# schema.net
KiCad netlist of a schematic drawn in EAGLE
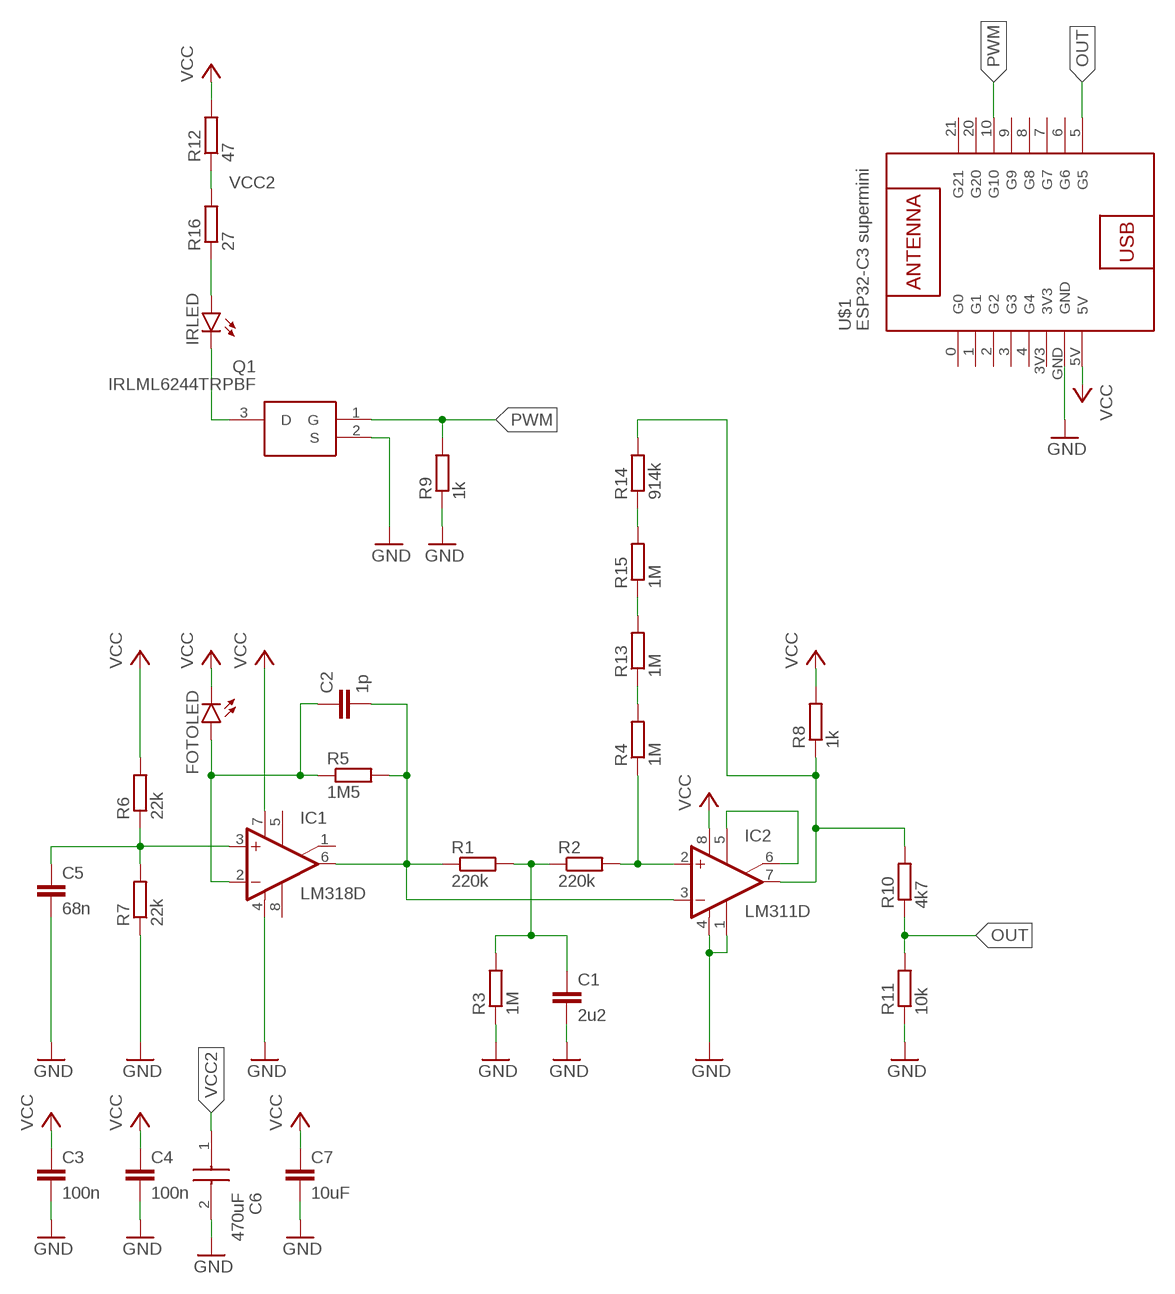
[diagram p0: schematic, sheet 1]

(export (version "E")
  (design (tool "Eeschema 10.0.6"))
  (components
    (comp (ref "C1")
      (value "2u2")
      (footprint "eagle-import:C0603")
      (libsource (lib "eagle-import") (part "C-EUC0603"))
    )
    (comp (ref "C2")
      (value "1p")
      (footprint "eagle-import:C0603K")
      (libsource (lib "eagle-import") (part "C-EUC0603K"))
    )
    (comp (ref "C3")
      (value "100n")
      (footprint "eagle-import:C0603")
      (libsource (lib "eagle-import") (part "C-EUC0603"))
    )
    (comp (ref "C4")
      (value "100n")
      (footprint "eagle-import:C0603")
      (libsource (lib "eagle-import") (part "C-EUC0603"))
    )
    (comp (ref "C5")
      (value "68n")
      (footprint "eagle-import:C0603")
      (libsource (lib "eagle-import") (part "C-EUC0603"))
    )
    (comp (ref "C6")
      (value "470uF")
      (footprint "eagle-import:CAPAE830X1100N")
      (fields (field (name "MANUFACTURER_PART_NUMBER") "AEA0810101M035R"))
      (libsource (lib "eagle-import") (part "AEA0810101M035R"))
    )
    (comp (ref "C7")
      (value "10uF")
      (footprint "eagle-import:C0603")
      (libsource (lib "eagle-import") (part "C-EUC0603"))
    )
    (comp (ref "FOTOLED")
      (value "LED5MM")
      (footprint "eagle-import:LED5MM")
      (libsource (lib "eagle-import") (part "LED5MM"))
    )
    (comp (ref "IC1")
      (value "LM318D")
      (footprint "eagle-import:SO08")
      (libsource (lib "eagle-import") (part "LM318D"))
    )
    (comp (ref "IC2")
      (value "LM311D")
      (footprint "eagle-import:SO08")
      (libsource (lib "eagle-import") (part "LM311D"))
    )
    (comp (ref "IRLED")
      (value "LED5MM")
      (footprint "eagle-import:LED5MM")
      (libsource (lib "eagle-import") (part "LED5MM"))
    )
    (comp (ref "Q1")
      (value "IRLML6244TRPBF")
      (footprint "eagle-import:SOT95P237X112-3N")
      (libsource (lib "eagle-import") (part "IRLML6244TRPBF"))
    )
    (comp (ref "R1")
      (value "220k")
      (footprint "eagle-import:R0603")
      (libsource (lib "eagle-import") (part "R-EU_R0603"))
    )
    (comp (ref "R2")
      (value "220k")
      (footprint "eagle-import:R0603")
      (libsource (lib "eagle-import") (part "R-EU_R0603"))
    )
    (comp (ref "R3")
      (value "1M")
      (footprint "eagle-import:R0603")
      (libsource (lib "eagle-import") (part "R-EU_R0603"))
    )
    (comp (ref "R4")
      (value "1M")
      (footprint "eagle-import:R0603")
      (libsource (lib "eagle-import") (part "R-EU_R0603"))
    )
    (comp (ref "R5")
      (value "1M5")
      (footprint "eagle-import:R0603")
      (libsource (lib "eagle-import") (part "R-EU_R0603"))
    )
    (comp (ref "R6")
      (value "22k")
      (footprint "eagle-import:R0603")
      (libsource (lib "eagle-import") (part "R-EU_R0603"))
    )
    (comp (ref "R7")
      (value "22k")
      (footprint "eagle-import:R0603")
      (libsource (lib "eagle-import") (part "R-EU_R0603"))
    )
    (comp (ref "R8")
      (value "1k")
      (footprint "eagle-import:R0603")
      (libsource (lib "eagle-import") (part "R-EU_R0603"))
    )
    (comp (ref "R9")
      (value "1k")
      (footprint "eagle-import:R0603")
      (libsource (lib "eagle-import") (part "R-EU_R0603"))
    )
    (comp (ref "R10")
      (value "4k7")
      (footprint "eagle-import:R0603")
      (libsource (lib "eagle-import") (part "R-EU_R0603"))
    )
    (comp (ref "R11")
      (value "10k")
      (footprint "eagle-import:R0603")
      (libsource (lib "eagle-import") (part "R-EU_R0603"))
    )
    (comp (ref "R12")
      (value "47")
      (footprint "eagle-import:R0805")
      (libsource (lib "eagle-import") (part "R-EU_R0805"))
    )
    (comp (ref "R13")
      (value "1M")
      (footprint "eagle-import:R0603")
      (libsource (lib "eagle-import") (part "R-EU_R0603"))
    )
    (comp (ref "R14")
      (value "914k")
      (footprint "eagle-import:R0603")
      (libsource (lib "eagle-import") (part "R-EU_R0603"))
    )
    (comp (ref "R15")
      (value "1M")
      (footprint "eagle-import:R0603")
      (libsource (lib "eagle-import") (part "R-EU_R0603"))
    )
    (comp (ref "R16")
      (value "27")
      (footprint "eagle-import:R0805")
      (libsource (lib "eagle-import") (part "R-EU_R0805"))
    )
    (comp (ref "U$1")
      (value "ESP32-C3 supermini")
      (footprint "eagle-import:ESP32-C3_SUPERMINI")
      (libsource (lib "eagle-import") (part "ESP32-C3_SUPERMINI"))
    )
  )
  (nets
    (net (code "1") (name "/3V3") (class "Default")
      (node (ref "U$1") (pin "3V3") (pinfunction "3V3_3V3") (pintype "power_in"))
    )
    (net (code "2") (name "GND") (class "Default")
      (node (ref "C1") (pin "2") (pinfunction "2_2") (pintype "passive"))
      (node (ref "C3") (pin "2") (pinfunction "2_2") (pintype "passive"))
      (node (ref "C4") (pin "2") (pinfunction "2_2") (pintype "passive"))
      (node (ref "C5") (pin "2") (pinfunction "2_2") (pintype "passive"))
      (node (ref "C6") (pin "2") (pinfunction "-_2") (pintype "bidirectional"))
      (node (ref "C7") (pin "2") (pinfunction "2_2") (pintype "passive"))
      (node (ref "IC1") (pin "4") (pinfunction "V-_4") (pintype "power_in"))
      (node (ref "IC2") (pin "1") (pinfunction "GND_1") (pintype "passive"))
      (node (ref "IC2") (pin "4") (pinfunction "V-_4") (pintype "power_in"))
      (node (ref "Q1") (pin "2") (pinfunction "S_2") (pintype "bidirectional"))
      (node (ref "R11") (pin "1") (pinfunction "1_1") (pintype "passive"))
      (node (ref "R3") (pin "1") (pinfunction "1_1") (pintype "passive"))
      (node (ref "R7") (pin "1") (pinfunction "1_1") (pintype "passive"))
      (node (ref "R9") (pin "1") (pinfunction "1_1") (pintype "passive"))
      (node (ref "U$1") (pin "GND") (pinfunction "GND_GND") (pintype "power_in"))
    )
    (net (code "3") (name "Net-(C1-Pad1)") (class "Default")
      (node (ref "C1") (pin "1") (pinfunction "1_1") (pintype "passive"))
      (node (ref "R1") (pin "2") (pinfunction "2_2") (pintype "passive"))
      (node (ref "R2") (pin "1") (pinfunction "1_1") (pintype "passive"))
      (node (ref "R3") (pin "2") (pinfunction "2_2") (pintype "passive"))
    )
    (net (code "4") (name "Net-(IC1-+IN)") (class "Default")
      (node (ref "C5") (pin "1") (pinfunction "1_1") (pintype "passive"))
      (node (ref "IC1") (pin "3") (pinfunction "+IN_3") (pintype "input"))
      (node (ref "R6") (pin "1") (pinfunction "1_1") (pintype "passive"))
      (node (ref "R7") (pin "2") (pinfunction "2_2") (pintype "passive"))
    )
    (net (code "5") (name "Net-(IC1--IN)") (class "Default")
      (node (ref "C2") (pin "1") (pinfunction "1_1") (pintype "passive"))
      (node (ref "FOTOLED") (pin "A") (pinfunction "A_A") (pintype "passive"))
      (node (ref "IC1") (pin "2") (pinfunction "-IN_2") (pintype "input"))
      (node (ref "R5") (pin "1") (pinfunction "1_1") (pintype "passive"))
    )
    (net (code "6") (name "Net-(IC1-OUT)") (class "Default")
      (node (ref "C2") (pin "2") (pinfunction "2_2") (pintype "passive"))
      (node (ref "IC1") (pin "6") (pinfunction "OUT_6") (pintype "output"))
      (node (ref "IC2") (pin "3") (pinfunction "-IN_3") (pintype "input"))
      (node (ref "R1") (pin "1") (pinfunction "1_1") (pintype "passive"))
      (node (ref "R5") (pin "2") (pinfunction "2_2") (pintype "passive"))
    )
    (net (code "7") (name "Net-(IC2-+IN)") (class "Default")
      (node (ref "IC2") (pin "2") (pinfunction "+IN_2") (pintype "input"))
      (node (ref "R2") (pin "2") (pinfunction "2_2") (pintype "passive"))
      (node (ref "R4") (pin "1") (pinfunction "1_1") (pintype "passive"))
    )
    (net (code "8") (name "Net-(IC2-ON)") (class "Default")
      (node (ref "IC2") (pin "5") (pinfunction "ON_5") (pintype "passive"))
      (node (ref "IC2") (pin "6") (pinfunction "ON/STR_6") (pintype "passive"))
    )
    (net (code "9") (name "Net-(IC2-OUT)") (class "Default")
      (node (ref "IC2") (pin "7") (pinfunction "OUT_7") (pintype "output"))
      (node (ref "R10") (pin "2") (pinfunction "2_2") (pintype "passive"))
      (node (ref "R14") (pin "2") (pinfunction "2_2") (pintype "passive"))
      (node (ref "R8") (pin "1") (pinfunction "1_1") (pintype "passive"))
    )
    (net (code "10") (name "Net-(IRLED-C)") (class "Default")
      (node (ref "IRLED") (pin "K") (pinfunction "C_K") (pintype "passive"))
      (node (ref "Q1") (pin "3") (pinfunction "D_3") (pintype "bidirectional"))
    )
    (net (code "11") (name "Net-(IRLED-PadA)") (class "Default")
      (node (ref "IRLED") (pin "A") (pinfunction "A_A") (pintype "passive"))
      (node (ref "R16") (pin "1") (pinfunction "1_1") (pintype "passive"))
    )
    (net (code "12") (name "Net-(R13-Pad1)") (class "Default")
      (node (ref "R13") (pin "1") (pinfunction "1_1") (pintype "passive"))
      (node (ref "R4") (pin "2") (pinfunction "2_2") (pintype "passive"))
    )
    (net (code "13") (name "Net-(R13-Pad2)") (class "Default")
      (node (ref "R13") (pin "2") (pinfunction "2_2") (pintype "passive"))
      (node (ref "R15") (pin "1") (pinfunction "1_1") (pintype "passive"))
    )
    (net (code "14") (name "Net-(R14-Pad1)") (class "Default")
      (node (ref "R14") (pin "1") (pinfunction "1_1") (pintype "passive"))
      (node (ref "R15") (pin "2") (pinfunction "2_2") (pintype "passive"))
    )
    (net (code "15") (name "OUT") (class "Default")
      (node (ref "R10") (pin "1") (pinfunction "1_1") (pintype "passive"))
      (node (ref "R11") (pin "2") (pinfunction "2_2") (pintype "passive"))
      (node (ref "U$1") (pin "5") (pinfunction "G5_5") (pintype "bidirectional"))
    )
    (net (code "16") (name "PWM") (class "Default")
      (node (ref "Q1") (pin "1") (pinfunction "G_1") (pintype "bidirectional"))
      (node (ref "R9") (pin "2") (pinfunction "2_2") (pintype "passive"))
      (node (ref "U$1") (pin "10") (pinfunction "G10_10") (pintype "bidirectional"))
    )
    (net (code "17") (name "VCC") (class "Default")
      (node (ref "C3") (pin "1") (pinfunction "1_1") (pintype "passive"))
      (node (ref "C4") (pin "1") (pinfunction "1_1") (pintype "passive"))
      (node (ref "C7") (pin "1") (pinfunction "1_1") (pintype "passive"))
      (node (ref "FOTOLED") (pin "K") (pinfunction "C_K") (pintype "passive"))
      (node (ref "IC1") (pin "7") (pinfunction "V+_7") (pintype "power_in"))
      (node (ref "IC2") (pin "8") (pinfunction "V+_8") (pintype "power_in"))
      (node (ref "R12") (pin "2") (pinfunction "2_2") (pintype "passive"))
      (node (ref "R6") (pin "2") (pinfunction "2_2") (pintype "passive"))
      (node (ref "R8") (pin "2") (pinfunction "2_2") (pintype "passive"))
      (node (ref "U$1") (pin "5V") (pinfunction "5V_5V") (pintype "power_in"))
    )
    (net (code "18") (name "VCC2") (class "Default")
      (node (ref "C6") (pin "1") (pinfunction "+_1") (pintype "bidirectional"))
      (node (ref "R12") (pin "1") (pinfunction "1_1") (pintype "passive"))
      (node (ref "R16") (pin "2") (pinfunction "2_2") (pintype "passive"))
    )
    (net (code "19") (name "unconnected-(IC1-CMP-Pad8)") (class "Default")
      (node (ref "IC1") (pin "8") (pinfunction "CMP_8") (pintype "passive"))
    )
    (net (code "20") (name "unconnected-(IC1-ON-Pad5)") (class "Default")
      (node (ref "IC1") (pin "5") (pinfunction "ON_5") (pintype "passive"))
    )
    (net (code "21") (name "unconnected-(IC1-ON{slash}CMP-Pad1)") (class "Default")
      (node (ref "IC1") (pin "1") (pinfunction "ON/CMP_1") (pintype "passive"))
    )
    (net (code "22") (name "unconnected-(U$1-G0-Pad0)") (class "Default")
      (node (ref "U$1") (pin "0") (pinfunction "G0_0") (pintype "bidirectional"))
    )
    (net (code "23") (name "unconnected-(U$1-G1-Pad1)") (class "Default")
      (node (ref "U$1") (pin "1") (pinfunction "G1_1") (pintype "bidirectional"))
    )
    (net (code "24") (name "unconnected-(U$1-G2-Pad2)") (class "Default")
      (node (ref "U$1") (pin "2") (pinfunction "G2_2") (pintype "bidirectional"))
    )
    (net (code "25") (name "unconnected-(U$1-G3-Pad3)") (class "Default")
      (node (ref "U$1") (pin "3") (pinfunction "G3_3") (pintype "bidirectional"))
    )
    (net (code "26") (name "unconnected-(U$1-G4-Pad4)") (class "Default")
      (node (ref "U$1") (pin "4") (pinfunction "G4_4") (pintype "bidirectional"))
    )
    (net (code "27") (name "unconnected-(U$1-G6-Pad6)") (class "Default")
      (node (ref "U$1") (pin "6") (pinfunction "G6_6") (pintype "bidirectional"))
    )
    (net (code "28") (name "unconnected-(U$1-G7-Pad7)") (class "Default")
      (node (ref "U$1") (pin "7") (pinfunction "G7_7") (pintype "bidirectional"))
    )
    (net (code "29") (name "unconnected-(U$1-G8-Pad8)") (class "Default")
      (node (ref "U$1") (pin "8") (pinfunction "G8_8") (pintype "bidirectional"))
    )
    (net (code "30") (name "unconnected-(U$1-G9-Pad9)") (class "Default")
      (node (ref "U$1") (pin "9") (pinfunction "G9_9") (pintype "bidirectional"))
    )
    (net (code "31") (name "unconnected-(U$1-G20-Pad20)") (class "Default")
      (node (ref "U$1") (pin "20") (pinfunction "G20_20") (pintype "bidirectional"))
    )
    (net (code "32") (name "unconnected-(U$1-G21-Pad21)") (class "Default")
      (node (ref "U$1") (pin "21") (pinfunction "G21_21") (pintype "bidirectional"))
    )
  )
)
